# moduloComunicacao4_1-smd.net
KiCad netlist of a schematic drawn in EAGLE
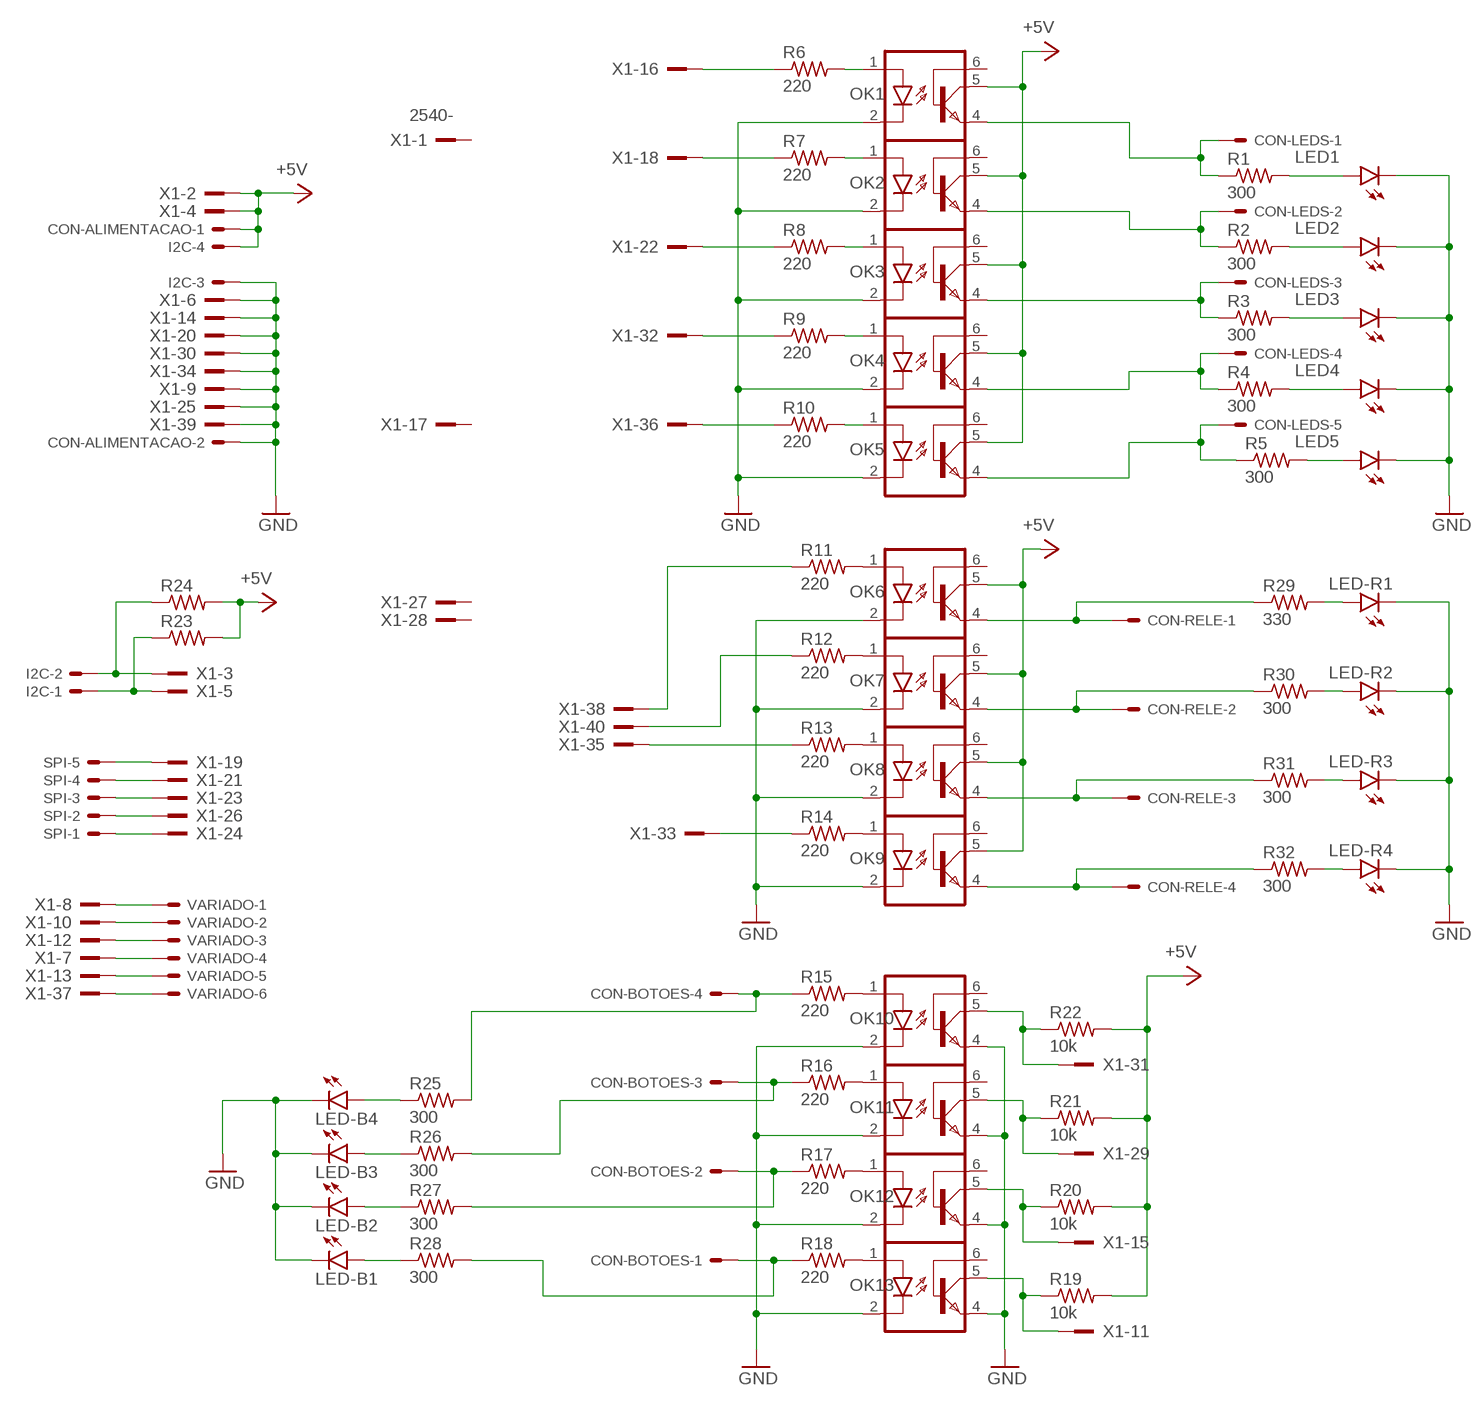
[diagram p0: schematic, sheet 1]

(export (version "E")
  (design (tool "Eeschema 10.0.6"))
  (components
    (comp (ref "CON-ALIMENTACAO")
      (value "22-23-2021")
      (footprint "eagle-import:22-23-2021")
      (fields (field (name "MF") "MOLEX"))
      (libsource (lib "eagle-import") (part "22-23-2021"))
    )
    (comp (ref "CON-BOTOES")
      (value "22-23-2041")
      (footprint "eagle-import:22-23-2041")
      (fields (field (name "MF") "MOLEX"))
      (libsource (lib "eagle-import") (part "22-23-2041"))
    )
    (comp (ref "CON-LEDS")
      (value "22-23-2051")
      (footprint "eagle-import:22-23-2051")
      (fields (field (name "MF") "MOLEX"))
      (libsource (lib "eagle-import") (part "22-23-2051"))
    )
    (comp (ref "CON-RELE")
      (value "22-23-2041")
      (footprint "eagle-import:22-23-2041")
      (fields (field (name "MF") "MOLEX"))
      (libsource (lib "eagle-import") (part "22-23-2041"))
    )
    (comp (ref "I2C")
      (value "22-23-2041")
      (footprint "eagle-import:22-23-2041")
      (fields (field (name "MF") "MOLEX"))
      (libsource (lib "eagle-import") (part "22-23-2041"))
    )
    (comp (ref "LED-B1")
      (value "LEDCHIP-LED0805")
      (footprint "eagle-import:CHIP-LED0805")
      (libsource (lib "eagle-import") (part "LEDCHIP-LED0805"))
    )
    (comp (ref "LED-B2")
      (value "LEDCHIP-LED0805")
      (footprint "eagle-import:CHIP-LED0805")
      (libsource (lib "eagle-import") (part "LEDCHIP-LED0805"))
    )
    (comp (ref "LED-B3")
      (value "LEDCHIP-LED0805")
      (footprint "eagle-import:CHIP-LED0805")
      (libsource (lib "eagle-import") (part "LEDCHIP-LED0805"))
    )
    (comp (ref "LED-B4")
      (value "LEDCHIP-LED0805")
      (footprint "eagle-import:CHIP-LED0805")
      (libsource (lib "eagle-import") (part "LEDCHIP-LED0805"))
    )
    (comp (ref "LED-R1")
      (value "LEDCHIP-LED0805")
      (footprint "eagle-import:CHIP-LED0805")
      (libsource (lib "eagle-import") (part "LEDCHIP-LED0805"))
    )
    (comp (ref "LED-R2")
      (value "LEDCHIP-LED0805")
      (footprint "eagle-import:CHIP-LED0805")
      (libsource (lib "eagle-import") (part "LEDCHIP-LED0805"))
    )
    (comp (ref "LED-R3")
      (value "LEDCHIP-LED0805")
      (footprint "eagle-import:CHIP-LED0805")
      (libsource (lib "eagle-import") (part "LEDCHIP-LED0805"))
    )
    (comp (ref "LED-R4")
      (value "LEDCHIP-LED0805")
      (footprint "eagle-import:CHIP-LED0805")
      (libsource (lib "eagle-import") (part "LEDCHIP-LED0805"))
    )
    (comp (ref "LED1")
      (value "LED5MM")
      (footprint "eagle-import:LED5MM")
      (libsource (lib "eagle-import") (part "LED5MM"))
    )
    (comp (ref "LED2")
      (value "LED5MM")
      (footprint "eagle-import:LED5MM")
      (libsource (lib "eagle-import") (part "LED5MM"))
    )
    (comp (ref "LED3")
      (value "LED5MM")
      (footprint "eagle-import:LED5MM")
      (libsource (lib "eagle-import") (part "LED5MM"))
    )
    (comp (ref "LED4")
      (value "LED5MM")
      (footprint "eagle-import:LED5MM")
      (libsource (lib "eagle-import") (part "LED5MM"))
    )
    (comp (ref "LED5")
      (value "LED5MM")
      (footprint "eagle-import:LED5MM")
      (libsource (lib "eagle-import") (part "LED5MM"))
    )
    (comp (ref "OK1")
      (value "4N25M")
      (footprint "eagle-import:DIL06")
      (fields (field (name "MPN") "4N25-M"))
      (libsource (lib "eagle-import") (part "4N?M25"))
    )
    (comp (ref "OK2")
      (value "4N25M")
      (footprint "eagle-import:DIL06")
      (fields (field (name "MPN") "4N25-M"))
      (libsource (lib "eagle-import") (part "4N?M25"))
    )
    (comp (ref "OK3")
      (value "4N25M")
      (footprint "eagle-import:DIL06")
      (fields (field (name "MPN") "4N25-M"))
      (libsource (lib "eagle-import") (part "4N?M25"))
    )
    (comp (ref "OK4")
      (value "4N25M")
      (footprint "eagle-import:DIL06")
      (fields (field (name "MPN") "4N25-M"))
      (libsource (lib "eagle-import") (part "4N?M25"))
    )
    (comp (ref "OK5")
      (value "4N25M")
      (footprint "eagle-import:DIL06")
      (fields (field (name "MPN") "4N25-M"))
      (libsource (lib "eagle-import") (part "4N?M25"))
    )
    (comp (ref "OK6")
      (value "4N25M")
      (footprint "eagle-import:DIL06")
      (fields (field (name "MPN") "4N25-M"))
      (libsource (lib "eagle-import") (part "4N?M25"))
    )
    (comp (ref "OK7")
      (value "4N25M")
      (footprint "eagle-import:DIL06")
      (fields (field (name "MPN") "4N25-M"))
      (libsource (lib "eagle-import") (part "4N?M25"))
    )
    (comp (ref "OK8")
      (value "4N25M")
      (footprint "eagle-import:DIL06")
      (fields (field (name "MPN") "4N25-M"))
      (libsource (lib "eagle-import") (part "4N?M25"))
    )
    (comp (ref "OK9")
      (value "4N25M")
      (footprint "eagle-import:DIL06")
      (fields (field (name "MPN") "4N25-M"))
      (libsource (lib "eagle-import") (part "4N?M25"))
    )
    (comp (ref "OK10")
      (value "4N25M")
      (footprint "eagle-import:DIL06")
      (fields (field (name "MPN") "4N25-M"))
      (libsource (lib "eagle-import") (part "4N?M25"))
    )
    (comp (ref "OK11")
      (value "4N25M")
      (footprint "eagle-import:DIL06")
      (fields (field (name "MPN") "4N25-M"))
      (libsource (lib "eagle-import") (part "4N?M25"))
    )
    (comp (ref "OK12")
      (value "4N25M")
      (footprint "eagle-import:DIL06")
      (fields (field (name "MPN") "4N25-M"))
      (libsource (lib "eagle-import") (part "4N?M25"))
    )
    (comp (ref "OK13")
      (value "4N25M")
      (footprint "eagle-import:DIL06")
      (fields (field (name "MPN") "4N25-M"))
      (libsource (lib "eagle-import") (part "4N?M25"))
    )
    (comp (ref "R1")
      (value "300")
      (footprint "eagle-import:0207_12")
      (libsource (lib "eagle-import") (part "R-US_0207/12"))
    )
    (comp (ref "R2")
      (value "300")
      (footprint "eagle-import:0207_12")
      (libsource (lib "eagle-import") (part "R-US_0207/12"))
    )
    (comp (ref "R3")
      (value "300")
      (footprint "eagle-import:0207_12")
      (libsource (lib "eagle-import") (part "R-US_0207/12"))
    )
    (comp (ref "R4")
      (value "300")
      (footprint "eagle-import:0207_12")
      (libsource (lib "eagle-import") (part "R-US_0207/12"))
    )
    (comp (ref "R5")
      (value "300")
      (footprint "eagle-import:0207_12")
      (libsource (lib "eagle-import") (part "R-US_0207/12"))
    )
    (comp (ref "R6")
      (value "220")
      (footprint "eagle-import:0204_7")
      (libsource (lib "eagle-import") (part "R-US_0204/7"))
    )
    (comp (ref "R7")
      (value "220")
      (footprint "eagle-import:0204_7")
      (libsource (lib "eagle-import") (part "R-US_0204/7"))
    )
    (comp (ref "R8")
      (value "220")
      (footprint "eagle-import:0204_7")
      (libsource (lib "eagle-import") (part "R-US_0204/7"))
    )
    (comp (ref "R9")
      (value "220")
      (footprint "eagle-import:0204_7")
      (libsource (lib "eagle-import") (part "R-US_0204/7"))
    )
    (comp (ref "R10")
      (value "220")
      (footprint "eagle-import:0204_7")
      (libsource (lib "eagle-import") (part "R-US_0204/7"))
    )
    (comp (ref "R11")
      (value "220")
      (footprint "eagle-import:0204_7")
      (libsource (lib "eagle-import") (part "R-US_0204/7"))
    )
    (comp (ref "R12")
      (value "220")
      (footprint "eagle-import:0204_7")
      (libsource (lib "eagle-import") (part "R-US_0204/7"))
    )
    (comp (ref "R13")
      (value "220")
      (footprint "eagle-import:0204_7")
      (libsource (lib "eagle-import") (part "R-US_0204/7"))
    )
    (comp (ref "R14")
      (value "220")
      (footprint "eagle-import:0204_7")
      (libsource (lib "eagle-import") (part "R-US_0204/7"))
    )
    (comp (ref "R15")
      (value "220")
      (footprint "eagle-import:0207_10")
      (libsource (lib "eagle-import") (part "R-US_0207/10"))
    )
    (comp (ref "R16")
      (value "220")
      (footprint "eagle-import:0207_10")
      (libsource (lib "eagle-import") (part "R-US_0207/10"))
    )
    (comp (ref "R17")
      (value "220")
      (footprint "eagle-import:0207_10")
      (libsource (lib "eagle-import") (part "R-US_0207/10"))
    )
    (comp (ref "R18")
      (value "220")
      (footprint "eagle-import:0207_10")
      (libsource (lib "eagle-import") (part "R-US_0207/10"))
    )
    (comp (ref "R19")
      (value "10k")
      (footprint "eagle-import:0204_7")
      (libsource (lib "eagle-import") (part "R-US_0204/7"))
    )
    (comp (ref "R20")
      (value "10k")
      (footprint "eagle-import:0204_7")
      (libsource (lib "eagle-import") (part "R-US_0204/7"))
    )
    (comp (ref "R21")
      (value "10k")
      (footprint "eagle-import:0204_7")
      (libsource (lib "eagle-import") (part "R-US_0204/7"))
    )
    (comp (ref "R22")
      (value "10k")
      (footprint "eagle-import:0204_7")
      (libsource (lib "eagle-import") (part "R-US_0204/7"))
    )
    (comp (ref "R23")
      (value "R-US_0204/5")
      (footprint "eagle-import:0204_5")
      (libsource (lib "eagle-import") (part "R-US_0204/5"))
    )
    (comp (ref "R24")
      (value "R-US_0204/5")
      (footprint "eagle-import:0204_5")
      (libsource (lib "eagle-import") (part "R-US_0204/5"))
    )
    (comp (ref "R25")
      (value "300")
      (footprint "eagle-import:R0805")
      (libsource (lib "eagle-import") (part "R-US_R0805"))
    )
    (comp (ref "R26")
      (value "300")
      (footprint "eagle-import:R0805")
      (libsource (lib "eagle-import") (part "R-US_R0805"))
    )
    (comp (ref "R27")
      (value "300")
      (footprint "eagle-import:R0805")
      (libsource (lib "eagle-import") (part "R-US_R0805"))
    )
    (comp (ref "R28")
      (value "300")
      (footprint "eagle-import:R0805")
      (libsource (lib "eagle-import") (part "R-US_R0805"))
    )
    (comp (ref "R29")
      (value "330")
      (footprint "eagle-import:R0805")
      (libsource (lib "eagle-import") (part "R-US_R0805"))
    )
    (comp (ref "R30")
      (value "300")
      (footprint "eagle-import:R0805")
      (libsource (lib "eagle-import") (part "R-US_R0805"))
    )
    (comp (ref "R31")
      (value "300")
      (footprint "eagle-import:R0805")
      (libsource (lib "eagle-import") (part "R-US_R0805"))
    )
    (comp (ref "R32")
      (value "300")
      (footprint "eagle-import:R0805")
      (libsource (lib "eagle-import") (part "R-US_R0805"))
    )
    (comp (ref "SPI")
      (value "22-23-2051")
      (footprint "eagle-import:22-23-2051")
      (fields (field (name "MF") "MOLEX"))
      (libsource (lib "eagle-import") (part "22-23-2051"))
    )
    (comp (ref "VARIADO")
      (value "22-23-2061")
      (footprint "eagle-import:22-23-2061")
      (fields (field (name "MF") "MOLEX"))
      (libsource (lib "eagle-import") (part "22-23-2061"))
    )
    (comp (ref "X1")
      (value "2540-")
      (footprint "eagle-import:PAK100_2500-40")
      (libsource (lib "eagle-import") (part "2540-"))
    )
  )
  (nets
    (net (code "1") (name "+5V") (class "Default")
      (node (ref "CON-ALIMENTACAO") (pin "1") (pinfunction "S_1") (pintype "passive"))
      (node (ref "I2C") (pin "4") (pinfunction "S_4") (pintype "passive"))
      (node (ref "OK1") (pin "5") (pinfunction "COL_5") (pintype "passive"))
      (node (ref "OK2") (pin "5") (pinfunction "COL_5") (pintype "passive"))
      (node (ref "OK3") (pin "5") (pinfunction "COL_5") (pintype "passive"))
      (node (ref "OK4") (pin "5") (pinfunction "COL_5") (pintype "passive"))
      (node (ref "OK5") (pin "5") (pinfunction "COL_5") (pintype "passive"))
      (node (ref "OK6") (pin "5") (pinfunction "COL_5") (pintype "passive"))
      (node (ref "OK7") (pin "5") (pinfunction "COL_5") (pintype "passive"))
      (node (ref "OK8") (pin "5") (pinfunction "COL_5") (pintype "passive"))
      (node (ref "OK9") (pin "5") (pinfunction "COL_5") (pintype "passive"))
      (node (ref "R19") (pin "2") (pinfunction "2_2") (pintype "passive"))
      (node (ref "R20") (pin "2") (pinfunction "2_2") (pintype "passive"))
      (node (ref "R21") (pin "2") (pinfunction "2_2") (pintype "passive"))
      (node (ref "R22") (pin "2") (pinfunction "2_2") (pintype "passive"))
      (node (ref "R23") (pin "2") (pinfunction "2_2") (pintype "passive"))
      (node (ref "R24") (pin "2") (pinfunction "2_2") (pintype "passive"))
      (node (ref "X1") (pin "2") (pinfunction "KL_2") (pintype "passive"))
      (node (ref "X1") (pin "4") (pinfunction "KL_4") (pintype "passive"))
    )
    (net (code "2") (name "GND") (class "Default")
      (node (ref "CON-ALIMENTACAO") (pin "2") (pinfunction "S_2") (pintype "passive"))
      (node (ref "I2C") (pin "3") (pinfunction "S_3") (pintype "passive"))
      (node (ref "LED-B1") (pin "C") (pinfunction "C_C") (pintype "passive"))
      (node (ref "LED-B2") (pin "C") (pinfunction "C_C") (pintype "passive"))
      (node (ref "LED-B3") (pin "C") (pinfunction "C_C") (pintype "passive"))
      (node (ref "LED-B4") (pin "C") (pinfunction "C_C") (pintype "passive"))
      (node (ref "LED-R1") (pin "C") (pinfunction "C_C") (pintype "passive"))
      (node (ref "LED-R2") (pin "C") (pinfunction "C_C") (pintype "passive"))
      (node (ref "LED-R3") (pin "C") (pinfunction "C_C") (pintype "passive"))
      (node (ref "LED-R4") (pin "C") (pinfunction "C_C") (pintype "passive"))
      (node (ref "LED1") (pin "K") (pinfunction "C_K") (pintype "passive"))
      (node (ref "LED2") (pin "K") (pinfunction "C_K") (pintype "passive"))
      (node (ref "LED3") (pin "K") (pinfunction "C_K") (pintype "passive"))
      (node (ref "LED4") (pin "K") (pinfunction "C_K") (pintype "passive"))
      (node (ref "LED5") (pin "K") (pinfunction "C_K") (pintype "passive"))
      (node (ref "OK1") (pin "2") (pinfunction "C_2") (pintype "passive"))
      (node (ref "OK10") (pin "2") (pinfunction "C_2") (pintype "passive"))
      (node (ref "OK10") (pin "4") (pinfunction "EMI_4") (pintype "passive"))
      (node (ref "OK11") (pin "2") (pinfunction "C_2") (pintype "passive"))
      (node (ref "OK11") (pin "4") (pinfunction "EMI_4") (pintype "passive"))
      (node (ref "OK12") (pin "2") (pinfunction "C_2") (pintype "passive"))
      (node (ref "OK12") (pin "4") (pinfunction "EMI_4") (pintype "passive"))
      (node (ref "OK13") (pin "2") (pinfunction "C_2") (pintype "passive"))
      (node (ref "OK13") (pin "4") (pinfunction "EMI_4") (pintype "passive"))
      (node (ref "OK2") (pin "2") (pinfunction "C_2") (pintype "passive"))
      (node (ref "OK3") (pin "2") (pinfunction "C_2") (pintype "passive"))
      (node (ref "OK4") (pin "2") (pinfunction "C_2") (pintype "passive"))
      (node (ref "OK5") (pin "2") (pinfunction "C_2") (pintype "passive"))
      (node (ref "OK6") (pin "2") (pinfunction "C_2") (pintype "passive"))
      (node (ref "OK7") (pin "2") (pinfunction "C_2") (pintype "passive"))
      (node (ref "OK8") (pin "2") (pinfunction "C_2") (pintype "passive"))
      (node (ref "OK9") (pin "2") (pinfunction "C_2") (pintype "passive"))
      (node (ref "X1") (pin "14") (pinfunction "KL_14") (pintype "passive"))
      (node (ref "X1") (pin "20") (pinfunction "KL_20") (pintype "passive"))
      (node (ref "X1") (pin "25") (pinfunction "KL_25") (pintype "passive"))
      (node (ref "X1") (pin "30") (pinfunction "KL_30") (pintype "passive"))
      (node (ref "X1") (pin "34") (pinfunction "KL_34") (pintype "passive"))
      (node (ref "X1") (pin "39") (pinfunction "KL_39") (pintype "passive"))
      (node (ref "X1") (pin "6") (pinfunction "KL_6") (pintype "passive"))
      (node (ref "X1") (pin "9") (pinfunction "KL_9") (pintype "passive"))
    )
    (net (code "3") (name "Net-(CON-BOTOESA-S)") (class "Default")
      (node (ref "CON-BOTOES") (pin "1") (pinfunction "S_1") (pintype "passive"))
      (node (ref "R18") (pin "1") (pinfunction "1_1") (pintype "passive"))
      (node (ref "R28") (pin "2") (pinfunction "2_2") (pintype "passive"))
    )
    (net (code "4") (name "Net-(CON-BOTOESB-S)") (class "Default")
      (node (ref "CON-BOTOES") (pin "2") (pinfunction "S_2") (pintype "passive"))
      (node (ref "R17") (pin "1") (pinfunction "1_1") (pintype "passive"))
      (node (ref "R27") (pin "2") (pinfunction "2_2") (pintype "passive"))
    )
    (net (code "5") (name "Net-(CON-BOTOESC-S)") (class "Default")
      (node (ref "CON-BOTOES") (pin "3") (pinfunction "S_3") (pintype "passive"))
      (node (ref "R16") (pin "1") (pinfunction "1_1") (pintype "passive"))
      (node (ref "R26") (pin "2") (pinfunction "2_2") (pintype "passive"))
    )
    (net (code "6") (name "Net-(CON-BOTOESD-S)") (class "Default")
      (node (ref "CON-BOTOES") (pin "4") (pinfunction "S_4") (pintype "passive"))
      (node (ref "R15") (pin "1") (pinfunction "1_1") (pintype "passive"))
      (node (ref "R25") (pin "2") (pinfunction "2_2") (pintype "passive"))
    )
    (net (code "7") (name "Net-(CON-LEDSA-S)") (class "Default")
      (node (ref "CON-LEDS") (pin "1") (pinfunction "S_1") (pintype "passive"))
      (node (ref "OK1") (pin "4") (pinfunction "EMI_4") (pintype "passive"))
      (node (ref "R1") (pin "1") (pinfunction "1_1") (pintype "passive"))
    )
    (net (code "8") (name "Net-(CON-LEDSB-S)") (class "Default")
      (node (ref "CON-LEDS") (pin "2") (pinfunction "S_2") (pintype "passive"))
      (node (ref "OK2") (pin "4") (pinfunction "EMI_4") (pintype "passive"))
      (node (ref "R2") (pin "1") (pinfunction "1_1") (pintype "passive"))
    )
    (net (code "9") (name "Net-(CON-LEDSC-S)") (class "Default")
      (node (ref "CON-LEDS") (pin "3") (pinfunction "S_3") (pintype "passive"))
      (node (ref "OK3") (pin "4") (pinfunction "EMI_4") (pintype "passive"))
      (node (ref "R3") (pin "1") (pinfunction "1_1") (pintype "passive"))
    )
    (net (code "10") (name "Net-(CON-LEDSD-S)") (class "Default")
      (node (ref "CON-LEDS") (pin "4") (pinfunction "S_4") (pintype "passive"))
      (node (ref "OK4") (pin "4") (pinfunction "EMI_4") (pintype "passive"))
      (node (ref "R4") (pin "1") (pinfunction "1_1") (pintype "passive"))
    )
    (net (code "11") (name "Net-(CON-LEDSE-S)") (class "Default")
      (node (ref "CON-LEDS") (pin "5") (pinfunction "S_5") (pintype "passive"))
      (node (ref "OK5") (pin "4") (pinfunction "EMI_4") (pintype "passive"))
      (node (ref "R5") (pin "1") (pinfunction "1_1") (pintype "passive"))
    )
    (net (code "12") (name "Net-(CON-RELEA-S)") (class "Default")
      (node (ref "CON-RELE") (pin "1") (pinfunction "S_1") (pintype "passive"))
      (node (ref "OK6") (pin "4") (pinfunction "EMI_4") (pintype "passive"))
      (node (ref "R29") (pin "1") (pinfunction "1_1") (pintype "passive"))
    )
    (net (code "13") (name "Net-(CON-RELEB-S)") (class "Default")
      (node (ref "CON-RELE") (pin "2") (pinfunction "S_2") (pintype "passive"))
      (node (ref "OK7") (pin "4") (pinfunction "EMI_4") (pintype "passive"))
      (node (ref "R30") (pin "1") (pinfunction "1_1") (pintype "passive"))
    )
    (net (code "14") (name "Net-(CON-RELEC-S)") (class "Default")
      (node (ref "CON-RELE") (pin "3") (pinfunction "S_3") (pintype "passive"))
      (node (ref "OK8") (pin "4") (pinfunction "EMI_4") (pintype "passive"))
      (node (ref "R31") (pin "1") (pinfunction "1_1") (pintype "passive"))
    )
    (net (code "15") (name "Net-(CON-RELED-S)") (class "Default")
      (node (ref "CON-RELE") (pin "4") (pinfunction "S_4") (pintype "passive"))
      (node (ref "OK9") (pin "4") (pinfunction "EMI_4") (pintype "passive"))
      (node (ref "R32") (pin "1") (pinfunction "1_1") (pintype "passive"))
    )
    (net (code "16") (name "Net-(I2CA-S)") (class "Default")
      (node (ref "I2C") (pin "1") (pinfunction "S_1") (pintype "passive"))
      (node (ref "R23") (pin "1") (pinfunction "1_1") (pintype "passive"))
      (node (ref "X1") (pin "5") (pinfunction "KL_5") (pintype "passive"))
    )
    (net (code "17") (name "Net-(I2CB-S)") (class "Default")
      (node (ref "I2C") (pin "2") (pinfunction "S_2") (pintype "passive"))
      (node (ref "R24") (pin "1") (pinfunction "1_1") (pintype "passive"))
      (node (ref "X1") (pin "3") (pinfunction "KL_3") (pintype "passive"))
    )
    (net (code "18") (name "Net-(LED-B1-PadA)") (class "Default")
      (node (ref "LED-B1") (pin "A") (pinfunction "A_A") (pintype "passive"))
      (node (ref "R28") (pin "1") (pinfunction "1_1") (pintype "passive"))
    )
    (net (code "19") (name "Net-(LED-B2-PadA)") (class "Default")
      (node (ref "LED-B2") (pin "A") (pinfunction "A_A") (pintype "passive"))
      (node (ref "R27") (pin "1") (pinfunction "1_1") (pintype "passive"))
    )
    (net (code "20") (name "Net-(LED-B3-PadA)") (class "Default")
      (node (ref "LED-B3") (pin "A") (pinfunction "A_A") (pintype "passive"))
      (node (ref "R26") (pin "1") (pinfunction "1_1") (pintype "passive"))
    )
    (net (code "21") (name "Net-(LED-B4-PadA)") (class "Default")
      (node (ref "LED-B4") (pin "A") (pinfunction "A_A") (pintype "passive"))
      (node (ref "R25") (pin "1") (pinfunction "1_1") (pintype "passive"))
    )
    (net (code "22") (name "Net-(LED-R1-PadA)") (class "Default")
      (node (ref "LED-R1") (pin "A") (pinfunction "A_A") (pintype "passive"))
      (node (ref "R29") (pin "2") (pinfunction "2_2") (pintype "passive"))
    )
    (net (code "23") (name "Net-(LED-R2-PadA)") (class "Default")
      (node (ref "LED-R2") (pin "A") (pinfunction "A_A") (pintype "passive"))
      (node (ref "R30") (pin "2") (pinfunction "2_2") (pintype "passive"))
    )
    (net (code "24") (name "Net-(LED-R3-PadA)") (class "Default")
      (node (ref "LED-R3") (pin "A") (pinfunction "A_A") (pintype "passive"))
      (node (ref "R31") (pin "2") (pinfunction "2_2") (pintype "passive"))
    )
    (net (code "25") (name "Net-(LED-R4-PadA)") (class "Default")
      (node (ref "LED-R4") (pin "A") (pinfunction "A_A") (pintype "passive"))
      (node (ref "R32") (pin "2") (pinfunction "2_2") (pintype "passive"))
    )
    (net (code "26") (name "Net-(LED1-PadA)") (class "Default")
      (node (ref "LED1") (pin "A") (pinfunction "A_A") (pintype "passive"))
      (node (ref "R1") (pin "2") (pinfunction "2_2") (pintype "passive"))
    )
    (net (code "27") (name "Net-(LED2-PadA)") (class "Default")
      (node (ref "LED2") (pin "A") (pinfunction "A_A") (pintype "passive"))
      (node (ref "R2") (pin "2") (pinfunction "2_2") (pintype "passive"))
    )
    (net (code "28") (name "Net-(LED3-PadA)") (class "Default")
      (node (ref "LED3") (pin "A") (pinfunction "A_A") (pintype "passive"))
      (node (ref "R3") (pin "2") (pinfunction "2_2") (pintype "passive"))
    )
    (net (code "29") (name "Net-(LED4-PadA)") (class "Default")
      (node (ref "LED4") (pin "A") (pinfunction "A_A") (pintype "passive"))
      (node (ref "R4") (pin "2") (pinfunction "2_2") (pintype "passive"))
    )
    (net (code "30") (name "Net-(LED5-PadA)") (class "Default")
      (node (ref "LED5") (pin "A") (pinfunction "A_A") (pintype "passive"))
      (node (ref "R5") (pin "2") (pinfunction "2_2") (pintype "passive"))
    )
    (net (code "31") (name "Net-(OK1-A)") (class "Default")
      (node (ref "OK1") (pin "1") (pinfunction "A_1") (pintype "passive"))
      (node (ref "R6") (pin "2") (pinfunction "2_2") (pintype "passive"))
    )
    (net (code "32") (name "Net-(OK2-A)") (class "Default")
      (node (ref "OK2") (pin "1") (pinfunction "A_1") (pintype "passive"))
      (node (ref "R7") (pin "2") (pinfunction "2_2") (pintype "passive"))
    )
    (net (code "33") (name "Net-(OK3-A)") (class "Default")
      (node (ref "OK3") (pin "1") (pinfunction "A_1") (pintype "passive"))
      (node (ref "R8") (pin "2") (pinfunction "2_2") (pintype "passive"))
    )
    (net (code "34") (name "Net-(OK4-A)") (class "Default")
      (node (ref "OK4") (pin "1") (pinfunction "A_1") (pintype "passive"))
      (node (ref "R9") (pin "2") (pinfunction "2_2") (pintype "passive"))
    )
    (net (code "35") (name "Net-(OK5-A)") (class "Default")
      (node (ref "OK5") (pin "1") (pinfunction "A_1") (pintype "passive"))
      (node (ref "R10") (pin "2") (pinfunction "2_2") (pintype "passive"))
    )
    (net (code "36") (name "Net-(OK6-A)") (class "Default")
      (node (ref "OK6") (pin "1") (pinfunction "A_1") (pintype "passive"))
      (node (ref "R11") (pin "2") (pinfunction "2_2") (pintype "passive"))
    )
    (net (code "37") (name "Net-(OK7-A)") (class "Default")
      (node (ref "OK7") (pin "1") (pinfunction "A_1") (pintype "passive"))
      (node (ref "R12") (pin "2") (pinfunction "2_2") (pintype "passive"))
    )
    (net (code "38") (name "Net-(OK8-A)") (class "Default")
      (node (ref "OK8") (pin "1") (pinfunction "A_1") (pintype "passive"))
      (node (ref "R13") (pin "2") (pinfunction "2_2") (pintype "passive"))
    )
    (net (code "39") (name "Net-(OK9-A)") (class "Default")
      (node (ref "OK9") (pin "1") (pinfunction "A_1") (pintype "passive"))
      (node (ref "R14") (pin "2") (pinfunction "2_2") (pintype "passive"))
    )
    (net (code "40") (name "Net-(OK10-A)") (class "Default")
      (node (ref "OK10") (pin "1") (pinfunction "A_1") (pintype "passive"))
      (node (ref "R15") (pin "2") (pinfunction "2_2") (pintype "passive"))
    )
    (net (code "41") (name "Net-(OK10-COL)") (class "Default")
      (node (ref "OK10") (pin "5") (pinfunction "COL_5") (pintype "passive"))
      (node (ref "R22") (pin "1") (pinfunction "1_1") (pintype "passive"))
      (node (ref "X1") (pin "31") (pinfunction "KL_31") (pintype "passive"))
    )
    (net (code "42") (name "Net-(OK11-A)") (class "Default")
      (node (ref "OK11") (pin "1") (pinfunction "A_1") (pintype "passive"))
      (node (ref "R16") (pin "2") (pinfunction "2_2") (pintype "passive"))
    )
    (net (code "43") (name "Net-(OK11-COL)") (class "Default")
      (node (ref "OK11") (pin "5") (pinfunction "COL_5") (pintype "passive"))
      (node (ref "R21") (pin "1") (pinfunction "1_1") (pintype "passive"))
      (node (ref "X1") (pin "29") (pinfunction "KL_29") (pintype "passive"))
    )
    (net (code "44") (name "Net-(OK12-A)") (class "Default")
      (node (ref "OK12") (pin "1") (pinfunction "A_1") (pintype "passive"))
      (node (ref "R17") (pin "2") (pinfunction "2_2") (pintype "passive"))
    )
    (net (code "45") (name "Net-(OK12-COL)") (class "Default")
      (node (ref "OK12") (pin "5") (pinfunction "COL_5") (pintype "passive"))
      (node (ref "R20") (pin "1") (pinfunction "1_1") (pintype "passive"))
      (node (ref "X1") (pin "15") (pinfunction "KL_15") (pintype "passive"))
    )
    (net (code "46") (name "Net-(OK13-A)") (class "Default")
      (node (ref "OK13") (pin "1") (pinfunction "A_1") (pintype "passive"))
      (node (ref "R18") (pin "2") (pinfunction "2_2") (pintype "passive"))
    )
    (net (code "47") (name "Net-(OK13-COL)") (class "Default")
      (node (ref "OK13") (pin "5") (pinfunction "COL_5") (pintype "passive"))
      (node (ref "R19") (pin "1") (pinfunction "1_1") (pintype "passive"))
      (node (ref "X1") (pin "11") (pinfunction "KL_11") (pintype "passive"))
    )
    (net (code "48") (name "Net-(SPIA-S)") (class "Default")
      (node (ref "SPI") (pin "1") (pinfunction "S_1") (pintype "passive"))
      (node (ref "X1") (pin "24") (pinfunction "KL_24") (pintype "passive"))
    )
    (net (code "49") (name "Net-(SPIB-S)") (class "Default")
      (node (ref "SPI") (pin "2") (pinfunction "S_2") (pintype "passive"))
      (node (ref "X1") (pin "26") (pinfunction "KL_26") (pintype "passive"))
    )
    (net (code "50") (name "Net-(SPIC-S)") (class "Default")
      (node (ref "SPI") (pin "3") (pinfunction "S_3") (pintype "passive"))
      (node (ref "X1") (pin "23") (pinfunction "KL_23") (pintype "passive"))
    )
    (net (code "51") (name "Net-(SPID-S)") (class "Default")
      (node (ref "SPI") (pin "4") (pinfunction "S_4") (pintype "passive"))
      (node (ref "X1") (pin "21") (pinfunction "KL_21") (pintype "passive"))
    )
    (net (code "52") (name "Net-(SPIE-S)") (class "Default")
      (node (ref "SPI") (pin "5") (pinfunction "S_5") (pintype "passive"))
      (node (ref "X1") (pin "19") (pinfunction "KL_19") (pintype "passive"))
    )
    (net (code "53") (name "Net-(VARIADOA-S)") (class "Default")
      (node (ref "VARIADO") (pin "1") (pinfunction "S_1") (pintype "passive"))
      (node (ref "X1") (pin "8") (pinfunction "KL_8") (pintype "passive"))
    )
    (net (code "54") (name "Net-(VARIADOB-S)") (class "Default")
      (node (ref "VARIADO") (pin "2") (pinfunction "S_2") (pintype "passive"))
      (node (ref "X1") (pin "10") (pinfunction "KL_10") (pintype "passive"))
    )
    (net (code "55") (name "Net-(VARIADOC-S)") (class "Default")
      (node (ref "VARIADO") (pin "3") (pinfunction "S_3") (pintype "passive"))
      (node (ref "X1") (pin "12") (pinfunction "KL_12") (pintype "passive"))
    )
    (net (code "56") (name "Net-(VARIADOD-S)") (class "Default")
      (node (ref "VARIADO") (pin "4") (pinfunction "S_4") (pintype "passive"))
      (node (ref "X1") (pin "7") (pinfunction "KL_7") (pintype "passive"))
    )
    (net (code "57") (name "Net-(VARIADOE-S)") (class "Default")
      (node (ref "VARIADO") (pin "5") (pinfunction "S_5") (pintype "passive"))
      (node (ref "X1") (pin "13") (pinfunction "KL_13") (pintype "passive"))
    )
    (net (code "58") (name "Net-(VARIADOF-S)") (class "Default")
      (node (ref "VARIADO") (pin "6") (pinfunction "S_6") (pintype "passive"))
      (node (ref "X1") (pin "37") (pinfunction "KL_37") (pintype "passive"))
    )
    (net (code "59") (name "Net-(X1AA-KL)") (class "Default")
      (node (ref "R14") (pin "1") (pinfunction "1_1") (pintype "passive"))
      (node (ref "X1") (pin "33") (pinfunction "KL_33") (pintype "passive"))
    )
    (net (code "60") (name "Net-(X1AC-KL)") (class "Default")
      (node (ref "R13") (pin "1") (pinfunction "1_1") (pintype "passive"))
      (node (ref "X1") (pin "35") (pinfunction "KL_35") (pintype "passive"))
    )
    (net (code "61") (name "Net-(X1AD-KL)") (class "Default")
      (node (ref "R10") (pin "1") (pinfunction "1_1") (pintype "passive"))
      (node (ref "X1") (pin "36") (pinfunction "KL_36") (pintype "passive"))
    )
    (net (code "62") (name "Net-(X1AF-KL)") (class "Default")
      (node (ref "R11") (pin "1") (pinfunction "1_1") (pintype "passive"))
      (node (ref "X1") (pin "38") (pinfunction "KL_38") (pintype "passive"))
    )
    (net (code "63") (name "Net-(X1AI-KL)") (class "Default")
      (node (ref "R12") (pin "1") (pinfunction "1_1") (pintype "passive"))
      (node (ref "X1") (pin "40") (pinfunction "KL_40") (pintype "passive"))
    )
    (net (code "64") (name "Net-(X1H-KL)") (class "Default")
      (node (ref "R6") (pin "1") (pinfunction "1_1") (pintype "passive"))
      (node (ref "X1") (pin "16") (pinfunction "KL_16") (pintype "passive"))
    )
    (net (code "65") (name "Net-(X1J-KL)") (class "Default")
      (node (ref "R7") (pin "1") (pinfunction "1_1") (pintype "passive"))
      (node (ref "X1") (pin "18") (pinfunction "KL_18") (pintype "passive"))
    )
    (net (code "66") (name "Net-(X1O-KL)") (class "Default")
      (node (ref "R8") (pin "1") (pinfunction "1_1") (pintype "passive"))
      (node (ref "X1") (pin "22") (pinfunction "KL_22") (pintype "passive"))
    )
    (net (code "67") (name "Net-(X1Z-KL)") (class "Default")
      (node (ref "R9") (pin "1") (pinfunction "1_1") (pintype "passive"))
      (node (ref "X1") (pin "32") (pinfunction "KL_32") (pintype "passive"))
    )
    (net (code "68") (name "unconnected-(OK1-BAS-Pad6)") (class "Default")
      (node (ref "OK1") (pin "6") (pinfunction "BAS_6") (pintype "passive"))
    )
    (net (code "69") (name "unconnected-(OK2-BAS-Pad6)") (class "Default")
      (node (ref "OK2") (pin "6") (pinfunction "BAS_6") (pintype "passive"))
    )
    (net (code "70") (name "unconnected-(OK3-BAS-Pad6)") (class "Default")
      (node (ref "OK3") (pin "6") (pinfunction "BAS_6") (pintype "passive"))
    )
    (net (code "71") (name "unconnected-(OK4-BAS-Pad6)") (class "Default")
      (node (ref "OK4") (pin "6") (pinfunction "BAS_6") (pintype "passive"))
    )
    (net (code "72") (name "unconnected-(OK5-BAS-Pad6)") (class "Default")
      (node (ref "OK5") (pin "6") (pinfunction "BAS_6") (pintype "passive"))
    )
    (net (code "73") (name "unconnected-(OK6-BAS-Pad6)") (class "Default")
      (node (ref "OK6") (pin "6") (pinfunction "BAS_6") (pintype "passive"))
    )
    (net (code "74") (name "unconnected-(OK7-BAS-Pad6)") (class "Default")
      (node (ref "OK7") (pin "6") (pinfunction "BAS_6") (pintype "passive"))
    )
    (net (code "75") (name "unconnected-(OK8-BAS-Pad6)") (class "Default")
      (node (ref "OK8") (pin "6") (pinfunction "BAS_6") (pintype "passive"))
    )
    (net (code "76") (name "unconnected-(OK9-BAS-Pad6)") (class "Default")
      (node (ref "OK9") (pin "6") (pinfunction "BAS_6") (pintype "passive"))
    )
    (net (code "77") (name "unconnected-(OK10-BAS-Pad6)") (class "Default")
      (node (ref "OK10") (pin "6") (pinfunction "BAS_6") (pintype "passive"))
    )
    (net (code "78") (name "unconnected-(OK11-BAS-Pad6)") (class "Default")
      (node (ref "OK11") (pin "6") (pinfunction "BAS_6") (pintype "passive"))
    )
    (net (code "79") (name "unconnected-(OK12-BAS-Pad6)") (class "Default")
      (node (ref "OK12") (pin "6") (pinfunction "BAS_6") (pintype "passive"))
    )
    (net (code "80") (name "unconnected-(OK13-BAS-Pad6)") (class "Default")
      (node (ref "OK13") (pin "6") (pinfunction "BAS_6") (pintype "passive"))
    )
    (net (code "81") (name "unconnected-(X1A-KL-Pad1)") (class "Default")
      (node (ref "X1") (pin "1") (pinfunction "KL_1") (pintype "passive"))
    )
    (net (code "82") (name "unconnected-(X1I-KL-Pad17)") (class "Default")
      (node (ref "X1") (pin "17") (pinfunction "KL_17") (pintype "passive"))
    )
    (net (code "83") (name "unconnected-(X1T-KL-Pad27)") (class "Default")
      (node (ref "X1") (pin "27") (pinfunction "KL_27") (pintype "passive"))
    )
    (net (code "84") (name "unconnected-(X1U-KL-Pad28)") (class "Default")
      (node (ref "X1") (pin "28") (pinfunction "KL_28") (pintype "passive"))
    )
  )
)
